# PCB1.net
KiCad netlist of a schematic drawn in Altium Designer
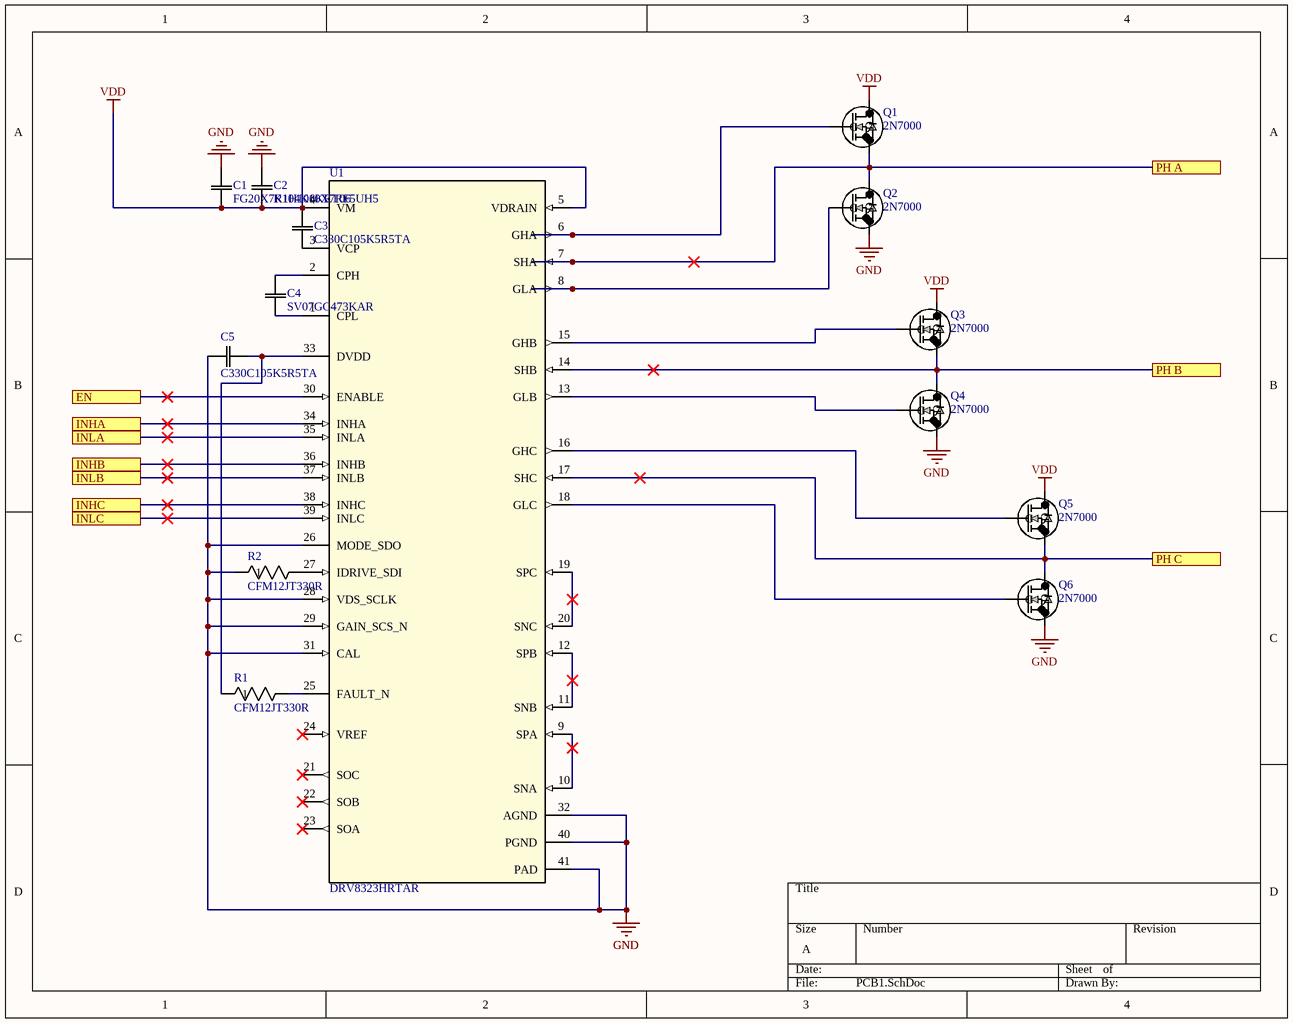
[diagram p0: PCB1.SchDoc]

(export (version "E")
  (design (tool "Eeschema 10.0.6"))
  (components
    (comp (ref "C1")
      (value "FG20X7R1H106KRT06")
      (footprint "CAP_FG20_TDK")
      (description "10 uF")
      (fields (field (name "COPYRIGHT") "Copyright (C) 2026 Ultra Librarian. All rights reserved."))
      (libsource (lib "Matthew Bracker") (part "FG20X7R1H106KRT06"))
    )
    (comp (ref "C2")
      (value "K104K10X7RF5UH5")
      (footprint "K104K10X7RF5UH5_VIS")
      (description "K 50V 100nF Â±10% X7R AMMO e3")
      (fields (field (name "COPYRIGHT") "Copyright (C) 2025 Ultra Librarian. All rights reserved."))
      (libsource (lib "Matthew Bracker") (part "K104K10X7RF5UH5"))
    )
    (comp (ref "C3")
      (value "C330C105K5R5TA")
      (footprint "CAP_C330C_MR_X7R_KEM")
      (description "1 uF")
      (fields (field (name "COPYRIGHT") "Copyright (C) 2025 Ultra Librarian. All rights reserved."))
      (libsource (lib "Matthew Bracker") (part "C330C105K5R5TA"))
    )
    (comp (ref "C4")
      (value "SV07GC473KAR")
      (footprint "SV07_AVX")
      (description ".047 uF")
      (fields (field (name "COPYRIGHT") "Copyright (C) 2025 Ultra Librarian. All rights reserved."))
      (libsource (lib "Matthew Bracker") (part "SV07GC473KAR"))
    )
    (comp (ref "C5")
      (value "C330C105K5R5TA")
      (footprint "CAP_C330C_MR_X7R_KEM")
      (description "1 uF")
      (fields (field (name "COPYRIGHT") "Copyright (C) 2025 Ultra Librarian. All rights reserved."))
      (libsource (lib "Matthew Bracker") (part "C330C105K5R5TA"))
    )
    (comp (ref "Q1")
      (value "2N7000")
      (footprint "Q_TO-92_135AN_OSI")
      (description "MOSFET TO92 N 60V 0.2A 5OHM 150C")
      (fields (field (name "COPYRIGHT") "Copyright (C) 2026 Ultra Librarian. All rights reserved."))
      (libsource (lib "Matthew Bracker") (part "2N7000"))
    )
    (comp (ref "Q2")
      (value "2N7000")
      (footprint "Q_TO-92_135AN_OSI")
      (description "MOSFET TO92 N 60V 0.2A 5OHM 150C")
      (fields (field (name "COPYRIGHT") "Copyright (C) 2026 Ultra Librarian. All rights reserved."))
      (libsource (lib "Matthew Bracker") (part "2N7000"))
    )
    (comp (ref "Q3")
      (value "2N7000")
      (footprint "Q_TO-92_135AN_OSI")
      (description "MOSFET TO92 N 60V 0.2A 5OHM 150C")
      (fields (field (name "COPYRIGHT") "Copyright (C) 2026 Ultra Librarian. All rights reserved."))
      (libsource (lib "Matthew Bracker") (part "2N7000"))
    )
    (comp (ref "Q4")
      (value "2N7000")
      (footprint "Q_TO-92_135AN_OSI")
      (description "MOSFET TO92 N 60V 0.2A 5OHM 150C")
      (fields (field (name "COPYRIGHT") "Copyright (C) 2026 Ultra Librarian. All rights reserved."))
      (libsource (lib "Matthew Bracker") (part "2N7000"))
    )
    (comp (ref "Q5")
      (value "2N7000")
      (footprint "Q_TO-92_135AN_OSI")
      (description "MOSFET TO92 N 60V 0.2A 5OHM 150C")
      (fields (field (name "COPYRIGHT") "Copyright (C) 2026 Ultra Librarian. All rights reserved."))
      (libsource (lib "Matthew Bracker") (part "2N7000"))
    )
    (comp (ref "Q6")
      (value "2N7000")
      (footprint "Q_TO-92_135AN_OSI")
      (description "MOSFET TO92 N 60V 0.2A 5OHM 150C")
      (fields (field (name "COPYRIGHT") "Copyright (C) 2026 Ultra Librarian. All rights reserved."))
      (libsource (lib "Matthew Bracker") (part "2N7000"))
    )
    (comp (ref "R1")
      (value "CFM12JT330R")
      (footprint "STA_CFM12_STP")
      (description "330 OHM RESISTOR")
      (fields (field (name "COPYRIGHT") "Copyright (C) 2026 Ultra Librarian. All rights reserved."))
      (libsource (lib "Matthew Bracker") (part "CFM12JT330R"))
    )
    (comp (ref "R2")
      (value "CFM12JT330R")
      (footprint "STA_CFM12_STP")
      (description "330 OHM RESISTOR")
      (fields (field (name "COPYRIGHT") "Copyright (C) 2026 Ultra Librarian. All rights reserved."))
      (libsource (lib "Matthew Bracker") (part "CFM12JT330R"))
    )
    (comp (ref "U1")
      (value "DRV8323HRTAR")
      (footprint "RTA0040B")
      (description "65-V max 3-phase smart gate driver with current shunt amplifiers 40-WQFN -40 to 125")
      (fields (field (name "COPYRIGHT") "Copyright (C) 2025 Ultra Librarian. All rights reserved."))
      (libsource (lib "Matthew Bracker") (part "DRV8323HRTAR"))
    )
  )
  (nets
    (net (code "1") (name "/EN") (class "Default")
      (node (ref "U1") (pin "30") (pinfunction "ENABLE_30") (pintype "input"))
    )
    (net (code "2") (name "/INHA") (class "Default")
      (node (ref "U1") (pin "34") (pinfunction "INHA_34") (pintype "input"))
    )
    (net (code "3") (name "/INHB") (class "Default")
      (node (ref "U1") (pin "36") (pinfunction "INHB_36") (pintype "input"))
    )
    (net (code "4") (name "/INHC") (class "Default")
      (node (ref "U1") (pin "38") (pinfunction "INHC_38") (pintype "input"))
    )
    (net (code "5") (name "/INLA") (class "Default")
      (node (ref "U1") (pin "35") (pinfunction "INLA_35") (pintype "input"))
    )
    (net (code "6") (name "/INLB") (class "Default")
      (node (ref "U1") (pin "37") (pinfunction "INLB_37") (pintype "input"))
    )
    (net (code "7") (name "/INLC") (class "Default")
      (node (ref "U1") (pin "39") (pinfunction "INLC_39") (pintype "input"))
    )
    (net (code "8") (name "/PH A") (class "Default")
      (node (ref "Q1") (pin "1") (pinfunction "S_1") (pintype "passive"))
      (node (ref "Q2") (pin "3") (pinfunction "D_3") (pintype "passive"))
      (node (ref "U1") (pin "7") (pinfunction "SHA_7") (pintype "input"))
    )
    (net (code "9") (name "/PH B") (class "Default")
      (node (ref "Q3") (pin "1") (pinfunction "S_1") (pintype "passive"))
      (node (ref "Q4") (pin "3") (pinfunction "D_3") (pintype "passive"))
      (node (ref "U1") (pin "14") (pinfunction "SHB_14") (pintype "input"))
    )
    (net (code "10") (name "/PH C") (class "Default")
      (node (ref "Q5") (pin "1") (pinfunction "S_1") (pintype "passive"))
      (node (ref "Q6") (pin "3") (pinfunction "D_3") (pintype "passive"))
      (node (ref "U1") (pin "17") (pinfunction "SHC_17") (pintype "input"))
    )
    (net (code "11") (name "GND") (class "Default")
      (node (ref "C1") (pin "2") (pinfunction "2_2") (pintype "passive"))
      (node (ref "C2") (pin "1") (pinfunction "1_1") (pintype "passive"))
      (node (ref "C5") (pin "2") (pinfunction "2_2") (pintype "passive"))
      (node (ref "Q2") (pin "1") (pinfunction "S_1") (pintype "passive"))
      (node (ref "Q4") (pin "1") (pinfunction "S_1") (pintype "passive"))
      (node (ref "Q6") (pin "1") (pinfunction "S_1") (pintype "passive"))
      (node (ref "R2") (pin "1") (pinfunction "1_1") (pintype "passive"))
      (node (ref "U1") (pin "26") (pinfunction "MODE_SDO_26") (pintype "passive"))
      (node (ref "U1") (pin "28") (pinfunction "VDS_SCLK_28") (pintype "input"))
      (node (ref "U1") (pin "29") (pinfunction "GAIN_SCS_N_29") (pintype "input"))
      (node (ref "U1") (pin "31") (pinfunction "CAL_31") (pintype "input"))
      (node (ref "U1") (pin "32") (pinfunction "AGND_32") (pintype "power_in"))
      (node (ref "U1") (pin "40") (pinfunction "PGND_40") (pintype "power_in"))
      (node (ref "U1") (pin "41") (pinfunction "PAD_41") (pintype "power_in"))
    )
    (net (code "12") (name "Net-(Q1-G)") (class "Default")
      (node (ref "Q1") (pin "2") (pinfunction "G_2") (pintype "passive"))
      (node (ref "U1") (pin "6") (pinfunction "GHA_6") (pintype "output"))
    )
    (net (code "13") (name "Net-(Q2-G)") (class "Default")
      (node (ref "Q2") (pin "2") (pinfunction "G_2") (pintype "passive"))
      (node (ref "U1") (pin "8") (pinfunction "GLA_8") (pintype "output"))
    )
    (net (code "14") (name "Net-(Q3-G)") (class "Default")
      (node (ref "Q3") (pin "2") (pinfunction "G_2") (pintype "passive"))
      (node (ref "U1") (pin "15") (pinfunction "GHB_15") (pintype "output"))
    )
    (net (code "15") (name "Net-(Q4-G)") (class "Default")
      (node (ref "Q4") (pin "2") (pinfunction "G_2") (pintype "passive"))
      (node (ref "U1") (pin "13") (pinfunction "GLB_13") (pintype "output"))
    )
    (net (code "16") (name "Net-(Q5-G)") (class "Default")
      (node (ref "Q5") (pin "2") (pinfunction "G_2") (pintype "passive"))
      (node (ref "U1") (pin "16") (pinfunction "GHC_16") (pintype "output"))
    )
    (net (code "17") (name "Net-(Q6-G)") (class "Default")
      (node (ref "Q6") (pin "2") (pinfunction "G_2") (pintype "passive"))
      (node (ref "U1") (pin "18") (pinfunction "GLC_18") (pintype "output"))
    )
    (net (code "18") (name "Net-(U1-CPH)") (class "Default")
      (node (ref "C4") (pin "2") (pinfunction "2_2") (pintype "passive"))
      (node (ref "U1") (pin "2") (pinfunction "CPH_2") (pintype "passive"))
    )
    (net (code "19") (name "Net-(U1-CPL)") (class "Default")
      (node (ref "C4") (pin "1") (pinfunction "1_1") (pintype "passive"))
      (node (ref "U1") (pin "1") (pinfunction "CPL_1") (pintype "passive"))
    )
    (net (code "20") (name "Net-(U1-DVDD)") (class "Default")
      (node (ref "C5") (pin "1") (pinfunction "1_1") (pintype "passive"))
      (node (ref "R1") (pin "1") (pinfunction "1_1") (pintype "passive"))
      (node (ref "U1") (pin "33") (pinfunction "DVDD_33") (pintype "power_in"))
    )
    (net (code "21") (name "Net-(U1-FAULT_N)") (class "Default")
      (node (ref "R1") (pin "2") (pinfunction "2_2") (pintype "passive"))
      (node (ref "U1") (pin "25") (pinfunction "FAULT_N_25") (pintype "open_collector"))
    )
    (net (code "22") (name "Net-(U1-IDRIVE_SDI)") (class "Default")
      (node (ref "R2") (pin "2") (pinfunction "2_2") (pintype "passive"))
      (node (ref "U1") (pin "27") (pinfunction "IDRIVE_SDI_27") (pintype "input"))
    )
    (net (code "23") (name "Net-(U1-SNA)") (class "Default")
      (node (ref "U1") (pin "10") (pinfunction "SNA_10") (pintype "input"))
      (node (ref "U1") (pin "9") (pinfunction "SPA_9") (pintype "input"))
    )
    (net (code "24") (name "Net-(U1-SNB)") (class "Default")
      (node (ref "U1") (pin "11") (pinfunction "SNB_11") (pintype "input"))
      (node (ref "U1") (pin "12") (pinfunction "SPB_12") (pintype "input"))
    )
    (net (code "25") (name "Net-(U1-SNC)") (class "Default")
      (node (ref "U1") (pin "19") (pinfunction "SPC_19") (pintype "input"))
      (node (ref "U1") (pin "20") (pinfunction "SNC_20") (pintype "input"))
    )
    (net (code "26") (name "Net-(U1-VCP)") (class "Default")
      (node (ref "C3") (pin "1") (pinfunction "1_1") (pintype "passive"))
      (node (ref "U1") (pin "3") (pinfunction "VCP_3") (pintype "power_in"))
    )
    (net (code "27") (name "VDD") (class "Default")
      (node (ref "C1") (pin "1") (pinfunction "1_1") (pintype "passive"))
      (node (ref "C2") (pin "2") (pinfunction "2_2") (pintype "passive"))
      (node (ref "C3") (pin "2") (pinfunction "2_2") (pintype "passive"))
      (node (ref "Q1") (pin "3") (pinfunction "D_3") (pintype "passive"))
      (node (ref "Q3") (pin "3") (pinfunction "D_3") (pintype "passive"))
      (node (ref "Q5") (pin "3") (pinfunction "D_3") (pintype "passive"))
      (node (ref "U1") (pin "4") (pinfunction "VM_4") (pintype "power_in"))
      (node (ref "U1") (pin "5") (pinfunction "VDRAIN_5") (pintype "input"))
    )
    (net (code "28") (name "unconnected-(U1-SOA-Pad23)") (class "Default")
      (node (ref "U1") (pin "23") (pinfunction "SOA_23") (pintype "output+no_connect"))
    )
    (net (code "29") (name "unconnected-(U1-SOB-Pad22)") (class "Default")
      (node (ref "U1") (pin "22") (pinfunction "SOB_22") (pintype "output+no_connect"))
    )
    (net (code "30") (name "unconnected-(U1-SOC-Pad21)") (class "Default")
      (node (ref "U1") (pin "21") (pinfunction "SOC_21") (pintype "output+no_connect"))
    )
    (net (code "31") (name "unconnected-(U1-VREF-Pad24)") (class "Default")
      (node (ref "U1") (pin "24") (pinfunction "VREF_24") (pintype "input+no_connect"))
    )
  )
)
